# MicroSpecSensorBoard_adc_V2_1.net
KiCad netlist of a schematic drawn in Altium Designer
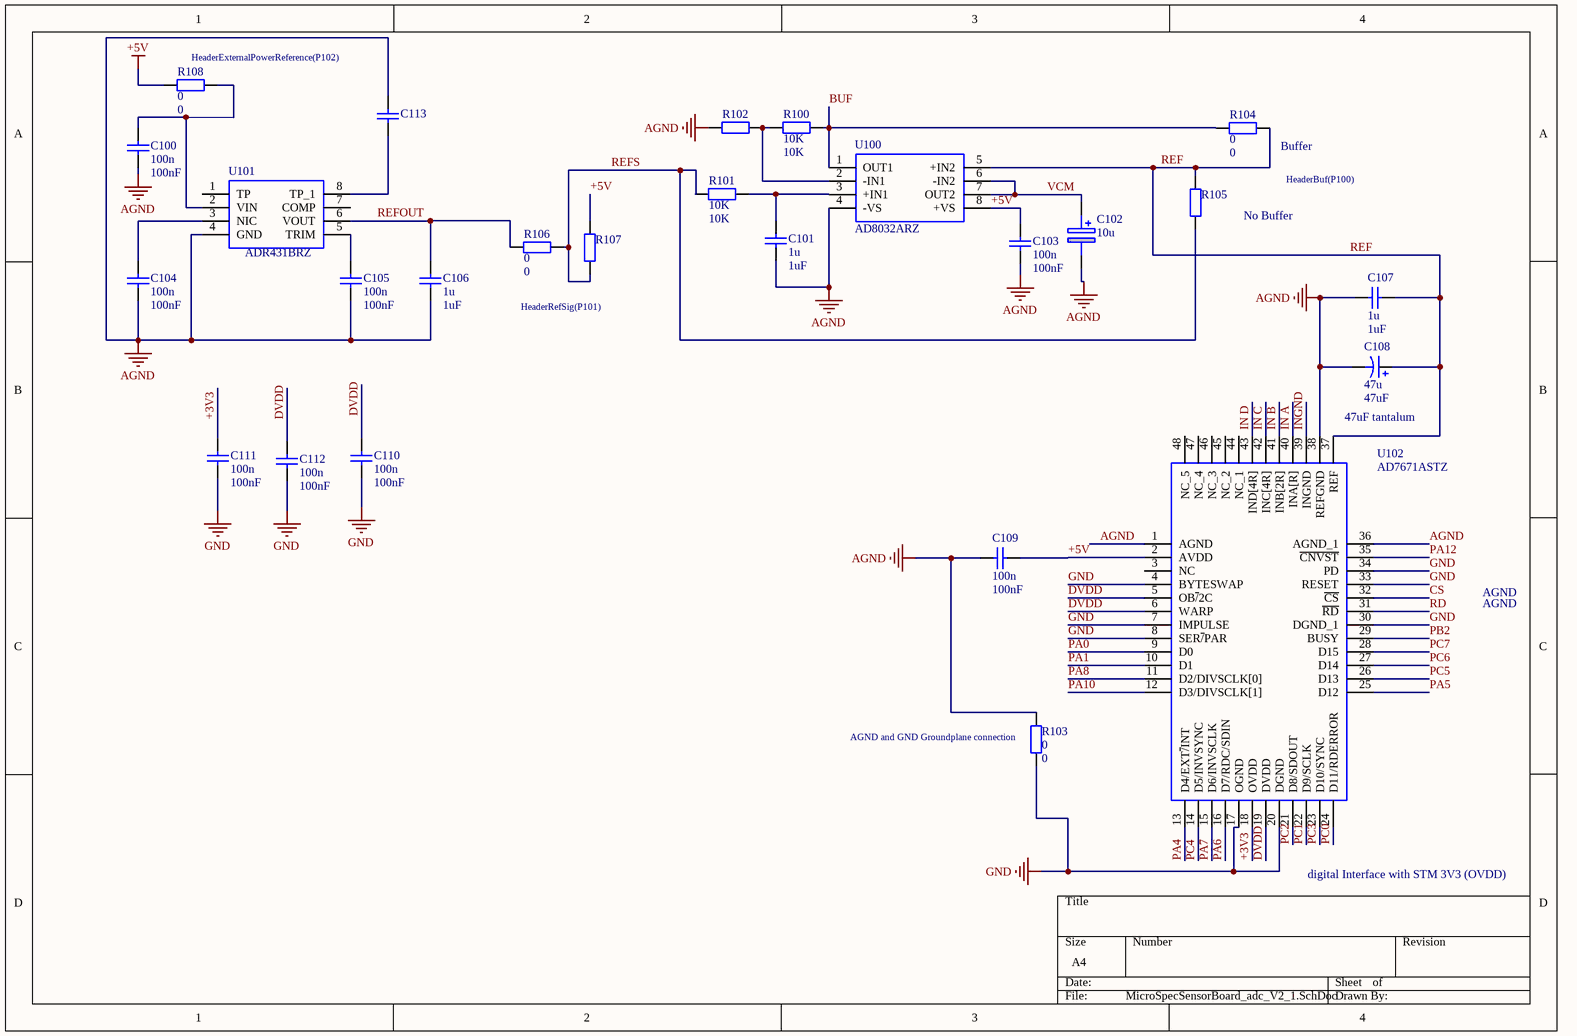
[diagram p0: MicroSpecSensorBoard_adc_V2_1.SchDoc]

(export (version "E")
  (design (tool "Eeschema 10.0.6"))
  (components
    (comp (ref "C100")
      (value "100n")
      (footprint "6-0805_L")
      (description "Capacitor")
      (fields (field (name "ALTIUM_VALUE") "100nF") (field (name "PUBLISHER") "Altium Limited"))
      (libsource (lib "USER_Library") (part "Cap"))
    )
    (comp (ref "C101")
      (value "1u")
      (footprint "6-0805_L")
      (description "Capacitor")
      (fields (field (name "ALTIUM_VALUE") "1uF") (field (name "PUBLISHER") "Altium Limited"))
      (libsource (lib "USER_Library") (part "Cap"))
    )
    (comp (ref "C102")
      (value "10u")
      (footprint "FKV(D)")
      (description "Ecap 10uF")
      (fields
        (field (name "RS PART NUMBER") "7083588P")
        (field (name "MANUFACTURER_PART_NUMBER") "EEEFK1J100P")
      )
      (libsource (lib "USER_Library") (part "EEEFK1J100P"))
    )
    (comp (ref "C103")
      (value "100n")
      (footprint "6-0805_L")
      (description "Capacitor")
      (fields (field (name "ALTIUM_VALUE") "100nF") (field (name "PUBLISHER") "Altium Limited"))
      (libsource (lib "USER_Library") (part "Cap"))
    )
    (comp (ref "C104")
      (value "100n")
      (footprint "6-0805_L")
      (description "Capacitor")
      (fields (field (name "ALTIUM_VALUE") "100nF") (field (name "PUBLISHER") "Altium Limited"))
      (libsource (lib "USER_Library") (part "Cap"))
    )
    (comp (ref "C105")
      (value "100n")
      (footprint "6-0805_L")
      (description "Capacitor")
      (fields (field (name "ALTIUM_VALUE") "100nF") (field (name "PUBLISHER") "Altium Limited"))
      (libsource (lib "USER_Library") (part "Cap"))
    )
    (comp (ref "C106")
      (value "1u")
      (footprint "6-0805_L")
      (description "Capacitor")
      (fields (field (name "ALTIUM_VALUE") "1uF") (field (name "PUBLISHER") "Altium Limited"))
      (libsource (lib "USER_Library") (part "Cap"))
    )
    (comp (ref "C107")
      (value "1u")
      (footprint "6-0805_L")
      (description "Capacitor")
      (fields (field (name "ALTIUM_VALUE") "1uF") (field (name "PUBLISHER") "Altium Limited"))
      (libsource (lib "USER_Library") (part "Cap"))
    )
    (comp (ref "C108")
      (value "47u")
      (footprint "CAPCP-3216-18N")
      (description "Polarized Capacitor (Axial)")
      (fields (field (name "ALTIUM_VALUE") "47uF") (field (name "PUBLISHER") "Altium Limited"))
      (libsource (lib "USER_Library") (part "Cap Pol2"))
    )
    (comp (ref "C109")
      (value "100n")
      (footprint "6-0805_L")
      (description "Capacitor")
      (fields (field (name "ALTIUM_VALUE") "100nF") (field (name "PUBLISHER") "Altium Limited"))
      (libsource (lib "USER_Library") (part "Cap"))
    )
    (comp (ref "C110")
      (value "100n")
      (footprint "6-0805_L")
      (description "Capacitor")
      (fields (field (name "ALTIUM_VALUE") "100nF") (field (name "PUBLISHER") "Altium Limited"))
      (libsource (lib "USER_Library") (part "Cap"))
    )
    (comp (ref "C111")
      (value "100n")
      (footprint "6-0805_L")
      (description "Capacitor")
      (fields (field (name "ALTIUM_VALUE") "100nF") (field (name "PUBLISHER") "Altium Limited"))
      (libsource (lib "USER_Library") (part "Cap"))
    )
    (comp (ref "C112")
      (value "100n")
      (footprint "6-0805_L")
      (description "Capacitor")
      (fields (field (name "ALTIUM_VALUE") "100nF") (field (name "PUBLISHER") "Altium Limited"))
      (libsource (lib "USER_Library") (part "Cap"))
    )
    (comp (ref "C113")
      (value "~")
      (footprint "6-0805_N")
      (description "Capacitor not populated")
      (fields (field (name "PUBLISHER") "Altium Limited"))
      (libsource (lib "USER_Library") (part "Cap_1"))
    )
    (comp (ref "R100")
      (value "10K")
      (footprint "6-0805_L")
      (description "Resistor")
      (fields (field (name "ALTIUM_VALUE") "10K") (field (name "PUBLISHER") "Altium Limited"))
      (libsource (lib "") (part "Res2_2"))
    )
    (comp (ref "R101")
      (value "10K")
      (footprint "6-0805_L")
      (description "Resistor")
      (fields (field (name "ALTIUM_VALUE") "10K") (field (name "PUBLISHER") "Altium Limited"))
      (libsource (lib "") (part "Res2_2"))
    )
    (comp (ref "R102")
      (value "~")
      (footprint "6-0805_L")
      (description "Resistor not populated")
      (fields (field (name "PUBLISHER") "Altium Limited"))
      (libsource (lib "") (part "Res2_2"))
    )
    (comp (ref "R103")
      (value "0")
      (footprint "6-0805_L")
      (description "Resistor")
      (fields (field (name "ALTIUM_VALUE") "0") (field (name "PUBLISHER") "Altium Limited"))
      (libsource (lib "USER_Library") (part "Res2"))
    )
    (comp (ref "R104")
      (value "0")
      (footprint "6-0805_L")
      (description "Resistor")
      (fields (field (name "ALTIUM_VALUE") "0") (field (name "PUBLISHER") "Altium Limited"))
      (libsource (lib "") (part "Res2_1"))
    )
    (comp (ref "R105")
      (value "~")
      (footprint "6-0805_L")
      (description "Resistor")
      (fields (field (name "PUBLISHER") "Altium Limited"))
      (libsource (lib "USER_Library") (part "Res2"))
    )
    (comp (ref "R106")
      (value "0")
      (footprint "6-0805_L")
      (description "Resistor")
      (fields (field (name "ALTIUM_VALUE") "0") (field (name "PUBLISHER") "Altium Limited"))
      (libsource (lib "") (part "Res2_1"))
    )
    (comp (ref "R107")
      (value "~")
      (footprint "6-0805_L")
      (description "Resistor")
      (fields (field (name "PUBLISHER") "Altium Limited"))
      (libsource (lib "USER_Library") (part "Res2"))
    )
    (comp (ref "R108")
      (value "0")
      (footprint "6-0805_L")
      (description "Resistor")
      (fields (field (name "ALTIUM_VALUE") "0") (field (name "PUBLISHER") "Altium Limited"))
      (libsource (lib "") (part "Res2_1"))
    )
    (comp (ref "U100")
      (value "AD8032ARZ")
      (footprint "SOIC127P600X175-8N")
      (description "Analog Devices AD8032ARZ, Dual Op Amp Rail-Rail, 5 V, 8-Pin SOIC")
      (fields (field (name "RS PART NUMBER") "0195105P"))
      (libsource (lib "USER_Library") (part "AD8032ARZ"))
    )
    (comp (ref "U101")
      (value "ADR431BRZ")
      (footprint "SOIC127P600X175-8N")
      (description "ADR431BRZ, Precision Voltage Reference 2.499 to 2.501V, 0.04% 30mA 20V max. 8-Pin SOIC")
      (fields (field (name "RS PART NUMBER") "9126366"))
      (libsource (lib "USER_Library") (part "ADR431BRZ"))
    )
    (comp (ref "U102")
      (value "AD7671ASTZ")
      (footprint "QFP50P900X900X160-48N")
      (description "AD7671ASTZ, 16-Bit Analogue to Digital Converter, Serial, 48-Pin LQFP")
      (fields (field (name "RS PART NUMBER") "1580250"))
      (libsource (lib "USER_Library") (part "AD7671ASTZ"))
    )
  )
  (nets
    (net (code "1") (name "+5V") (class "Default")
      (node (ref "C103") (pin "1") (pinfunction "1_1") (pintype "passive"))
      (node (ref "C109") (pin "2") (pinfunction "2_2") (pintype "passive"))
      (node (ref "R107") (pin "2") (pinfunction "2_2") (pintype "passive"))
      (node (ref "R108") (pin "2") (pinfunction "2_2") (pintype "passive"))
      (node (ref "U100") (pin "8") (pinfunction "+VS_8") (pintype "passive"))
      (node (ref "U102") (pin "2") (pinfunction "AVDD_2") (pintype "power_in"))
    )
    (net (code "2") (name "/+3V3") (class "Default")
      (node (ref "C111") (pin "1") (pinfunction "1_1") (pintype "passive"))
      (node (ref "U102") (pin "18") (pinfunction "OVDD_18") (pintype "power_in"))
    )
    (net (code "3") (name "/BUF") (class "Default")
      (node (ref "R100") (pin "2") (pinfunction "2_2") (pintype "passive"))
      (node (ref "R104") (pin "2") (pinfunction "2_2") (pintype "passive"))
      (node (ref "U100") (pin "1") (pinfunction "OUT1_1") (pintype "passive"))
    )
    (net (code "4") (name "/CS") (class "Default")
      (node (ref "U102") (pin "32") (pinfunction "CS_32") (pintype "passive"))
    )
    (net (code "5") (name "/DVDD") (class "Default")
      (node (ref "C110") (pin "1") (pinfunction "1_1") (pintype "passive"))
      (node (ref "C112") (pin "1") (pinfunction "1_1") (pintype "passive"))
      (node (ref "U102") (pin "19") (pinfunction "DVDD_19") (pintype "power_in"))
      (node (ref "U102") (pin "5") (pinfunction "OB~{/}2C_5") (pintype "passive"))
      (node (ref "U102") (pin "6") (pinfunction "WARP_6") (pintype "passive"))
    )
    (net (code "6") (name "/IN A") (class "Default")
      (node (ref "U102") (pin "40") (pinfunction "INA[R]_40") (pintype "passive"))
    )
    (net (code "7") (name "/IN B") (class "Default")
      (node (ref "U102") (pin "41") (pinfunction "INB[2R]_41") (pintype "passive"))
    )
    (net (code "8") (name "/IN C") (class "Default")
      (node (ref "U102") (pin "42") (pinfunction "INC[4R]_42") (pintype "passive"))
    )
    (net (code "9") (name "/IN D") (class "Default")
      (node (ref "U102") (pin "43") (pinfunction "IND[4R]_43") (pintype "passive"))
    )
    (net (code "10") (name "/INGND") (class "Default")
      (node (ref "U102") (pin "39") (pinfunction "INGND_39") (pintype "passive"))
    )
    (net (code "11") (name "/PA0") (class "Default")
      (node (ref "U102") (pin "9") (pinfunction "D0_9") (pintype "passive"))
    )
    (net (code "12") (name "/PA1") (class "Default")
      (node (ref "U102") (pin "10") (pinfunction "D1_10") (pintype "passive"))
    )
    (net (code "13") (name "/PA4") (class "Default")
      (node (ref "U102") (pin "13") (pinfunction "D4/EXT~{/}INT_13") (pintype "passive"))
    )
    (net (code "14") (name "/PA5") (class "Default")
      (node (ref "U102") (pin "25") (pinfunction "D12_25") (pintype "passive"))
    )
    (net (code "15") (name "/PA6") (class "Default")
      (node (ref "U102") (pin "16") (pinfunction "D7/RDC/SDIN_16") (pintype "passive"))
    )
    (net (code "16") (name "/PA7") (class "Default")
      (node (ref "U102") (pin "15") (pinfunction "D6/INVSCLK_15") (pintype "passive"))
    )
    (net (code "17") (name "/PA8") (class "Default")
      (node (ref "U102") (pin "11") (pinfunction "D2/DIVSCLK[0]_11") (pintype "passive"))
    )
    (net (code "18") (name "/PA10") (class "Default")
      (node (ref "U102") (pin "12") (pinfunction "D3/DIVSCLK[1]_12") (pintype "passive"))
    )
    (net (code "19") (name "/PA12") (class "Default")
      (node (ref "U102") (pin "35") (pinfunction "CNVST_35") (pintype "passive"))
    )
    (net (code "20") (name "/PB2") (class "Default")
      (node (ref "U102") (pin "29") (pinfunction "BUSY_29") (pintype "passive"))
    )
    (net (code "21") (name "/PC0") (class "Default")
      (node (ref "U102") (pin "24") (pinfunction "D11/RDERROR_24") (pintype "passive"))
    )
    (net (code "22") (name "/PC1") (class "Default")
      (node (ref "U102") (pin "22") (pinfunction "D9/SCLK_22") (pintype "passive"))
    )
    (net (code "23") (name "/PC2") (class "Default")
      (node (ref "U102") (pin "21") (pinfunction "D8/SDOUT_21") (pintype "passive"))
    )
    (net (code "24") (name "/PC3") (class "Default")
      (node (ref "U102") (pin "23") (pinfunction "D10/SYNC_23") (pintype "passive"))
    )
    (net (code "25") (name "/PC4") (class "Default")
      (node (ref "U102") (pin "14") (pinfunction "D5/INVSYNC_14") (pintype "passive"))
    )
    (net (code "26") (name "/PC5") (class "Default")
      (node (ref "U102") (pin "26") (pinfunction "D13_26") (pintype "passive"))
    )
    (net (code "27") (name "/PC6") (class "Default")
      (node (ref "U102") (pin "27") (pinfunction "D14_27") (pintype "passive"))
    )
    (net (code "28") (name "/PC7") (class "Default")
      (node (ref "U102") (pin "28") (pinfunction "D15_28") (pintype "passive"))
    )
    (net (code "29") (name "/RD") (class "Default")
      (node (ref "U102") (pin "31") (pinfunction "RD_31") (pintype "passive"))
    )
    (net (code "30") (name "/REF") (class "Default")
      (node (ref "C107") (pin "2") (pinfunction "2_2") (pintype "passive"))
      (node (ref "C108") (pin "1") (pinfunction "1_1") (pintype "passive"))
      (node (ref "R104") (pin "1") (pinfunction "1_1") (pintype "passive"))
      (node (ref "R105") (pin "2") (pinfunction "2_2") (pintype "passive"))
      (node (ref "U100") (pin "5") (pinfunction "+IN2_5") (pintype "passive"))
      (node (ref "U102") (pin "37") (pinfunction "REF_37") (pintype "passive"))
    )
    (net (code "32") (name "/REFOUT") (class "Default")
      (node (ref "C106") (pin "1") (pinfunction "1_1") (pintype "passive"))
      (node (ref "R106") (pin "2") (pinfunction "2_2") (pintype "passive"))
      (node (ref "U101") (pin "6") (pinfunction "VOUT_6") (pintype "passive"))
    )
    (net (code "33") (name "/REFS") (class "Default")
      (node (ref "R101") (pin "1") (pinfunction "1_1") (pintype "passive"))
      (node (ref "R105") (pin "1") (pinfunction "1_1") (pintype "passive"))
      (node (ref "R106") (pin "1") (pinfunction "1_1") (pintype "passive"))
      (node (ref "R107") (pin "1") (pinfunction "1_1") (pintype "passive"))
    )
    (net (code "34") (name "/VCM") (class "Default")
      (node (ref "C102") (pin "1") (pinfunction "+_1") (pintype "passive"))
      (node (ref "U100") (pin "6") (pinfunction "-IN2_6") (pintype "passive"))
      (node (ref "U100") (pin "7") (pinfunction "OUT2_7") (pintype "passive"))
    )
    (net (code "35") (name "AGND") (class "Default")
      (node (ref "C100") (pin "2") (pinfunction "2_2") (pintype "passive"))
      (node (ref "C101") (pin "2") (pinfunction "2_2") (pintype "passive"))
      (node (ref "C102") (pin "2") (pinfunction "-_2") (pintype "passive"))
      (node (ref "C103") (pin "2") (pinfunction "2_2") (pintype "passive"))
      (node (ref "C104") (pin "2") (pinfunction "2_2") (pintype "passive"))
      (node (ref "C105") (pin "2") (pinfunction "2_2") (pintype "passive"))
      (node (ref "C106") (pin "2") (pinfunction "2_2") (pintype "passive"))
      (node (ref "C107") (pin "1") (pinfunction "1_1") (pintype "passive"))
      (node (ref "C108") (pin "2") (pinfunction "2_2") (pintype "passive"))
      (node (ref "C109") (pin "1") (pinfunction "1_1") (pintype "passive"))
      (node (ref "C113") (pin "1") (pinfunction "1_1") (pintype "passive"))
      (node (ref "R102") (pin "1") (pinfunction "1_1") (pintype "passive"))
      (node (ref "R103") (pin "2") (pinfunction "2_2") (pintype "passive"))
      (node (ref "U100") (pin "4") (pinfunction "-VS_4") (pintype "passive"))
      (node (ref "U101") (pin "4") (pinfunction "GND_4") (pintype "passive"))
      (node (ref "U102") (pin "1") (pinfunction "AGND_1") (pintype "passive"))
      (node (ref "U102") (pin "36") (pinfunction "AGND_1_36") (pintype "passive"))
      (node (ref "U102") (pin "38") (pinfunction "REFGND_38") (pintype "passive"))
    )
    (net (code "36") (name "GND") (class "Default")
      (node (ref "C110") (pin "2") (pinfunction "2_2") (pintype "passive"))
      (node (ref "C111") (pin "2") (pinfunction "2_2") (pintype "passive"))
      (node (ref "C112") (pin "2") (pinfunction "2_2") (pintype "passive"))
      (node (ref "R103") (pin "1") (pinfunction "1_1") (pintype "passive"))
      (node (ref "U102") (pin "17") (pinfunction "OGND_17") (pintype "passive"))
      (node (ref "U102") (pin "20") (pinfunction "DGND_20") (pintype "passive"))
      (node (ref "U102") (pin "30") (pinfunction "DGND_1_30") (pintype "passive"))
      (node (ref "U102") (pin "33") (pinfunction "RESET_33") (pintype "passive"))
      (node (ref "U102") (pin "34") (pinfunction "PD_34") (pintype "passive"))
      (node (ref "U102") (pin "4") (pinfunction "BYTESWAP_4") (pintype "passive"))
      (node (ref "U102") (pin "7") (pinfunction "IMPULSE_7") (pintype "passive"))
      (node (ref "U102") (pin "8") (pinfunction "SER~{/}PAR_8") (pintype "passive"))
    )
    (net (code "37") (name "Net-(U100-+IN1)") (class "Default")
      (node (ref "C101") (pin "1") (pinfunction "1_1") (pintype "passive"))
      (node (ref "R101") (pin "2") (pinfunction "2_2") (pintype "passive"))
      (node (ref "U100") (pin "3") (pinfunction "+IN1_3") (pintype "passive"))
    )
    (net (code "38") (name "Net-(U100--IN1)") (class "Default")
      (node (ref "R100") (pin "1") (pinfunction "1_1") (pintype "passive"))
      (node (ref "R102") (pin "2") (pinfunction "2_2") (pintype "passive"))
      (node (ref "U100") (pin "2") (pinfunction "-IN1_2") (pintype "passive"))
    )
    (net (code "39") (name "Net-(U101-NIC)") (class "Default")
      (node (ref "C104") (pin "1") (pinfunction "1_1") (pintype "passive"))
      (node (ref "U101") (pin "3") (pinfunction "NIC_3") (pintype "passive"))
    )
    (net (code "40") (name "Net-(U101-TP_1)") (class "Default")
      (node (ref "C113") (pin "2") (pinfunction "2_2") (pintype "passive"))
      (node (ref "U101") (pin "8") (pinfunction "TP_1_8") (pintype "passive"))
    )
    (net (code "41") (name "Net-(U101-TRIM)") (class "Default")
      (node (ref "C105") (pin "1") (pinfunction "1_1") (pintype "passive"))
      (node (ref "U101") (pin "5") (pinfunction "TRIM_5") (pintype "passive"))
    )
    (net (code "42") (name "Net-(U101-VIN)") (class "Default")
      (node (ref "C100") (pin "1") (pinfunction "1_1") (pintype "passive"))
      (node (ref "R108") (pin "1") (pinfunction "1_1") (pintype "passive"))
      (node (ref "U101") (pin "2") (pinfunction "VIN_2") (pintype "passive"))
    )
    (net (code "43") (name "unconnected-(U101-COMP-Pad7)") (class "Default")
      (node (ref "U101") (pin "7") (pinfunction "COMP_7") (pintype "passive"))
    )
    (net (code "44") (name "unconnected-(U101-TP-Pad1)") (class "Default")
      (node (ref "U101") (pin "1") (pinfunction "TP_1") (pintype "passive"))
    )
    (net (code "45") (name "unconnected-(U102-NC-Pad3)") (class "Default")
      (node (ref "U102") (pin "3") (pinfunction "NC_3") (pintype "passive"))
    )
    (net (code "46") (name "unconnected-(U102-NC_1-Pad44)") (class "Default")
      (node (ref "U102") (pin "44") (pinfunction "NC_1_44") (pintype "passive"))
    )
    (net (code "47") (name "unconnected-(U102-NC_2-Pad45)") (class "Default")
      (node (ref "U102") (pin "45") (pinfunction "NC_2_45") (pintype "passive"))
    )
    (net (code "48") (name "unconnected-(U102-NC_3-Pad46)") (class "Default")
      (node (ref "U102") (pin "46") (pinfunction "NC_3_46") (pintype "passive"))
    )
    (net (code "49") (name "unconnected-(U102-NC_4-Pad47)") (class "Default")
      (node (ref "U102") (pin "47") (pinfunction "NC_4_47") (pintype "passive"))
    )
    (net (code "50") (name "unconnected-(U102-NC_5-Pad48)") (class "Default")
      (node (ref "U102") (pin "48") (pinfunction "NC_5_48") (pintype "passive"))
    )
  )
)
